# SMPS_Schematic.net
KiCad netlist of a schematic drawn in EAGLE
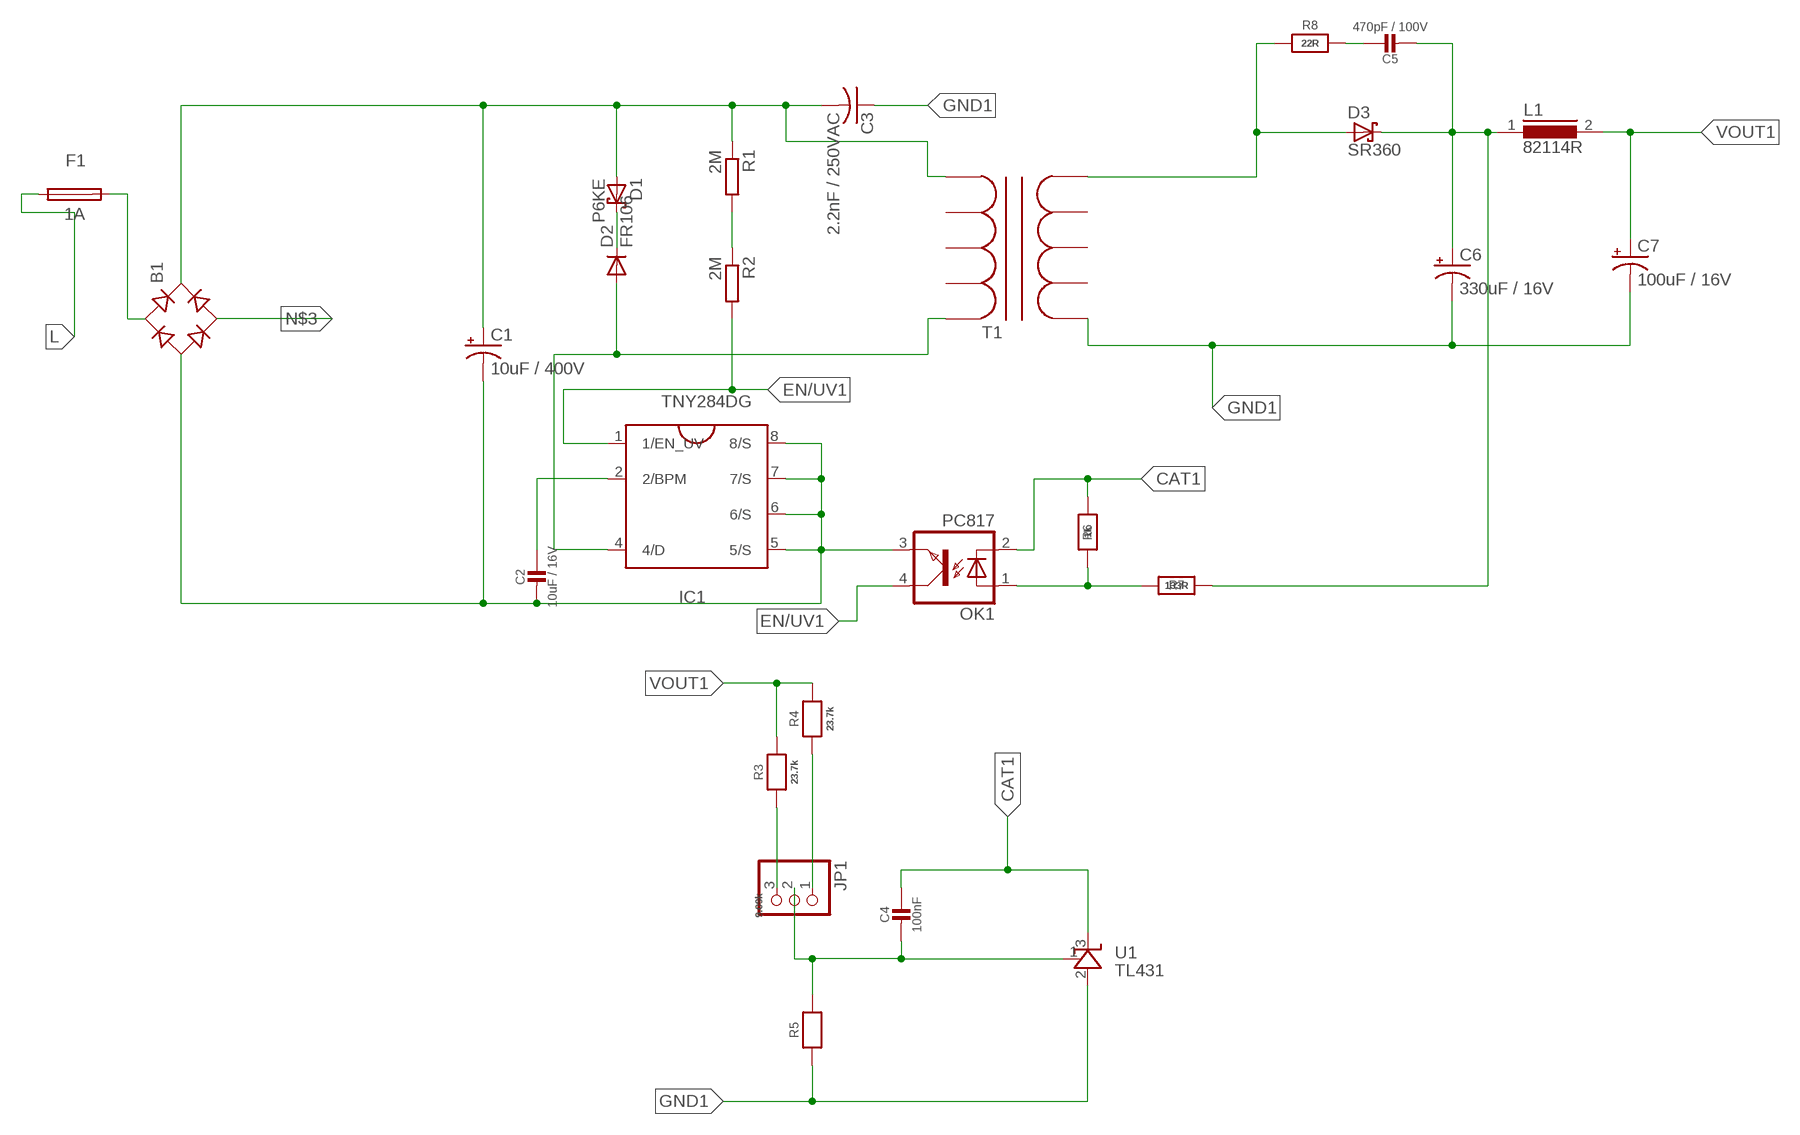
[diagram p0: schematic, sheet 1]

(export (version "E")
  (design (tool "Eeschema 10.0.6"))
  (components
    (comp (ref "B1")
      (value "B-DIL")
      (footprint "eagle-import:B-DIL")
      (libsource (lib "eagle-import") (part "B-DIL"))
    )
    (comp (ref "C1")
      (value "10uF / 400V")
      (footprint "eagle-import:E5-10,5")
      (libsource (lib "eagle-import") (part "CPOL-USE5-10.5"))
    )
    (comp (ref "C2")
      (value "10uF / 16V")
      (footprint "eagle-import:0805-NO")
      (libsource (lib "eagle-import") (part "CAP_CERAMIC0805-NOOUTLINE"))
    )
    (comp (ref "C3")
      (value "2.2nF / 250VAC")
      (footprint "eagle-import:C075-032X103")
      (libsource (lib "eagle-import") (part "C-US075-032X103"))
    )
    (comp (ref "C4")
      (value "100nF")
      (footprint "eagle-import:0805-NO")
      (libsource (lib "eagle-import") (part "CAP_CERAMIC0805-NOOUTLINE"))
    )
    (comp (ref "C5")
      (value "470pF / 100V")
      (footprint "eagle-import:0805-NO")
      (libsource (lib "eagle-import") (part "CAP_CERAMIC0805-NOOUTLINE"))
    )
    (comp (ref "C6")
      (value "330uF / 16V")
      (footprint "eagle-import:E3,5-8")
      (libsource (lib "eagle-import") (part "CPOL-USE3.5-8"))
    )
    (comp (ref "C7")
      (value "100uF / 16V")
      (footprint "eagle-import:E2,5-7")
      (libsource (lib "eagle-import") (part "CPOL-USE2.5-7"))
    )
    (comp (ref "D1")
      (value "P6KE")
      (footprint "eagle-import:CB417-15")
      (libsource (lib "eagle-import") (part "P6KEXX"))
    )
    (comp (ref "D2")
      (value "FR106")
      (footprint "eagle-import:DO41-10")
      (libsource (lib "eagle-import") (part "1N4004"))
    )
    (comp (ref "D3")
      (value "SR360")
      (footprint "eagle-import:C4111-15")
      (libsource (lib "eagle-import") (part "SCHOTTKY-DIODEC4111-15"))
    )
    (comp (ref "F1")
      (value "1A")
      (footprint "eagle-import:TR5")
      (libsource (lib "eagle-import") (part "TR5"))
    )
    (comp (ref "IC1")
      (value "TNY284DG")
      (footprint "eagle-import:SO8-C(D_PACKAGE)")
      (libsource (lib "eagle-import") (part "TNY375-380SO8-C"))
    )
    (comp (ref "JP1")
      (value "PINHD-1X3")
      (footprint "eagle-import:1X03")
      (libsource (lib "eagle-import") (part "PINHD-1X3"))
    )
    (comp (ref "L1")
      (value "82114R")
      (footprint "eagle-import:82114R")
      (libsource (lib "eagle-import") (part "82114R"))
    )
    (comp (ref "OK1")
      (value "PC817")
      (footprint "eagle-import:DIL04")
      (fields (field (name "MPN") "PC817X4J000F"))
      (libsource (lib "eagle-import") (part "PC817"))
    )
    (comp (ref "R1")
      (value "2M")
      (footprint "eagle-import:M1206")
      (libsource (lib "eagle-import") (part "R-EU_M1206"))
    )
    (comp (ref "R2")
      (value "2M")
      (footprint "eagle-import:M1206")
      (libsource (lib "eagle-import") (part "R-EU_M1206"))
    )
    (comp (ref "R3")
      (value "23.7k")
      (footprint "eagle-import:0805-NO")
      (libsource (lib "eagle-import") (part "RESISTOR0805_NOOUTLINE"))
    )
    (comp (ref "R4")
      (value "23.7k")
      (footprint "eagle-import:0805-NO")
      (libsource (lib "eagle-import") (part "RESISTOR0805_NOOUTLINE"))
    )
    (comp (ref "R5")
      (value "9.09k")
      (footprint "eagle-import:0805-NO")
      (libsource (lib "eagle-import") (part "RESISTOR0805_NOOUTLINE"))
    )
    (comp (ref "R6")
      (value "1k")
      (footprint "eagle-import:0805-NO")
      (libsource (lib "eagle-import") (part "RESISTOR0805_NOOUTLINE"))
    )
    (comp (ref "R7")
      (value "133R")
      (footprint "eagle-import:0805-NO")
      (libsource (lib "eagle-import") (part "RESISTOR0805_NOOUTLINE"))
    )
    (comp (ref "R8")
      (value "22R")
      (footprint "eagle-import:0805-NO")
      (libsource (lib "eagle-import") (part "RESISTOR0805_NOOUTLINE"))
    )
    (comp (ref "T1")
      (value "TRANSFORMER_EE16")
      (footprint "eagle-import:EE16")
      (libsource (lib "eagle-import") (part "TRANSFORMER_EE16"))
    )
    (comp (ref "U1")
      (value "TL431")
      (footprint "eagle-import:TO-92")
      (libsource (lib "eagle-import") (part "TL431"))
    )
  )
  (nets
    (net (code "1") (name "CAT1") (class "Default")
      (node (ref "C4") (pin "1") (pinfunction "1_1") (pintype "passive"))
      (node (ref "OK1") (pin "2") (pinfunction "C_2") (pintype "passive"))
      (node (ref "R6") (pin "1") (pinfunction "1_1") (pintype "passive"))
      (node (ref "U1") (pin "3") (pinfunction "C_3") (pintype "bidirectional"))
    )
    (net (code "2") (name "EN{slash}UV1") (class "Default")
      (node (ref "IC1") (pin "1") (pinfunction "1/EN_UV_1") (pintype "bidirectional"))
      (node (ref "OK1") (pin "4") (pinfunction "COL_4") (pintype "passive"))
      (node (ref "R2") (pin "2") (pinfunction "2_2") (pintype "passive"))
    )
    (net (code "3") (name "GND1") (class "Default")
      (node (ref "C3") (pin "1") (pinfunction "1_1") (pintype "passive"))
      (node (ref "C6") (pin "-") (pinfunction "-_-") (pintype "passive"))
      (node (ref "C7") (pin "-") (pinfunction "-_-") (pintype "passive"))
      (node (ref "R5") (pin "1") (pinfunction "1_1") (pintype "passive"))
      (node (ref "T1") (pin "P$6") (pinfunction "P$6_P$6") (pintype "bidirectional"))
      (node (ref "U1") (pin "2") (pinfunction "A_2") (pintype "bidirectional"))
    )
    (net (code "4") (name "L") (class "Default")
      (node (ref "F1") (pin "P$1") (pinfunction "1_P$1") (pintype "passive"))
    )
    (net (code "5") (name "N$3") (class "Default")
      (node (ref "B1") (pin "AC2") (pinfunction "AC2_AC2") (pintype "passive"))
    )
    (net (code "6") (name "Net-(B1-Pad+)") (class "Default")
      (node (ref "B1") (pin "+") (pinfunction "+_+") (pintype "passive"))
      (node (ref "C1") (pin "+") (pinfunction "+_+") (pintype "passive"))
      (node (ref "C3") (pin "2") (pinfunction "2_2") (pintype "passive"))
      (node (ref "D1") (pin "A") (pinfunction "A_A") (pintype "passive"))
      (node (ref "R1") (pin "1") (pinfunction "1_1") (pintype "passive"))
      (node (ref "T1") (pin "P$1") (pinfunction "P$1_P$1") (pintype "bidirectional"))
    )
    (net (code "7") (name "Net-(C5-Pad1)") (class "Default")
      (node (ref "C5") (pin "1") (pinfunction "1_1") (pintype "passive"))
      (node (ref "R8") (pin "2") (pinfunction "2_2") (pintype "passive"))
    )
    (net (code "8") (name "Net-(C5-Pad2)") (class "Default")
      (node (ref "C5") (pin "2") (pinfunction "2_2") (pintype "passive"))
      (node (ref "C6") (pin "+") (pinfunction "+_+") (pintype "passive"))
      (node (ref "D3") (pin "C") (pinfunction "C_C") (pintype "passive"))
      (node (ref "L1") (pin "1") (pinfunction "1_1") (pintype "passive"))
      (node (ref "R7") (pin "2") (pinfunction "2_2") (pintype "passive"))
    )
    (net (code "9") (name "Net-(D1-PadC)") (class "Default")
      (node (ref "D1") (pin "C") (pinfunction "C_C") (pintype "passive"))
      (node (ref "D2") (pin "C") (pinfunction "C_C") (pintype "passive"))
    )
    (net (code "10") (name "Net-(D3-PadA)") (class "Default")
      (node (ref "D3") (pin "A") (pinfunction "A_A") (pintype "passive"))
      (node (ref "R8") (pin "1") (pinfunction "1_1") (pintype "passive"))
      (node (ref "T1") (pin "P$10") (pinfunction "P$10_P$10") (pintype "bidirectional"))
    )
    (net (code "11") (name "Net-(F1-2)") (class "Default")
      (node (ref "B1") (pin "AC1") (pinfunction "AC1_AC1") (pintype "passive"))
      (node (ref "F1") (pin "P$2") (pinfunction "2_P$2") (pintype "passive"))
    )
    (net (code "12") (name "Net-(IC1-2{slash}BPM)") (class "Default")
      (node (ref "C2") (pin "1") (pinfunction "1_1") (pintype "passive"))
      (node (ref "IC1") (pin "2") (pinfunction "2/BPM_2") (pintype "bidirectional"))
    )
    (net (code "13") (name "Net-(IC1-4{slash}D)") (class "Default")
      (node (ref "D2") (pin "A") (pinfunction "A_A") (pintype "passive"))
      (node (ref "IC1") (pin "4") (pinfunction "4/D_4") (pintype "bidirectional"))
      (node (ref "T1") (pin "P$5") (pinfunction "P$5_P$5") (pintype "bidirectional"))
    )
    (net (code "14") (name "Net-(IC1-5{slash}S)") (class "Default")
      (node (ref "B1") (pin "-") (pinfunction "-_-") (pintype "passive"))
      (node (ref "C1") (pin "-") (pinfunction "-_-") (pintype "passive"))
      (node (ref "C2") (pin "2") (pinfunction "2_2") (pintype "passive"))
      (node (ref "IC1") (pin "5") (pinfunction "5/S_5") (pintype "bidirectional"))
      (node (ref "IC1") (pin "6") (pinfunction "6/S_6") (pintype "bidirectional"))
      (node (ref "IC1") (pin "7") (pinfunction "7/S_7") (pintype "bidirectional"))
      (node (ref "IC1") (pin "8") (pinfunction "8/S_8") (pintype "bidirectional"))
      (node (ref "OK1") (pin "3") (pinfunction "EMIT_3") (pintype "passive"))
    )
    (net (code "15") (name "Net-(JP1-Pad1)") (class "Default")
      (node (ref "JP1") (pin "1") (pinfunction "1_1") (pintype "passive"))
      (node (ref "R4") (pin "1") (pinfunction "1_1") (pintype "passive"))
    )
    (net (code "16") (name "Net-(JP1-Pad3)") (class "Default")
      (node (ref "JP1") (pin "3") (pinfunction "3_3") (pintype "passive"))
      (node (ref "R3") (pin "1") (pinfunction "1_1") (pintype "passive"))
    )
    (net (code "17") (name "Net-(OK1-A)") (class "Default")
      (node (ref "OK1") (pin "1") (pinfunction "A_1") (pintype "passive"))
      (node (ref "R6") (pin "2") (pinfunction "2_2") (pintype "passive"))
      (node (ref "R7") (pin "1") (pinfunction "1_1") (pintype "passive"))
    )
    (net (code "18") (name "Net-(R1-Pad2)") (class "Default")
      (node (ref "R1") (pin "2") (pinfunction "2_2") (pintype "passive"))
      (node (ref "R2") (pin "1") (pinfunction "1_1") (pintype "passive"))
    )
    (net (code "19") (name "Net-(U1-REF)") (class "Default")
      (node (ref "C4") (pin "2") (pinfunction "2_2") (pintype "passive"))
      (node (ref "JP1") (pin "2") (pinfunction "2_2") (pintype "passive"))
      (node (ref "R5") (pin "2") (pinfunction "2_2") (pintype "passive"))
      (node (ref "U1") (pin "1") (pinfunction "REF_1") (pintype "input"))
    )
    (net (code "20") (name "VOUT1") (class "Default")
      (node (ref "C7") (pin "+") (pinfunction "+_+") (pintype "passive"))
      (node (ref "L1") (pin "2") (pinfunction "2_2") (pintype "passive"))
      (node (ref "R3") (pin "2") (pinfunction "2_2") (pintype "passive"))
      (node (ref "R4") (pin "2") (pinfunction "2_2") (pintype "passive"))
    )
    (net (code "21") (name "unconnected-(T1-PadP$2)") (class "Default")
      (node (ref "T1") (pin "P$2") (pinfunction "P$2_P$2") (pintype "bidirectional"))
    )
    (net (code "22") (name "unconnected-(T1-PadP$3)") (class "Default")
      (node (ref "T1") (pin "P$3") (pinfunction "P$3_P$3") (pintype "bidirectional"))
    )
    (net (code "23") (name "unconnected-(T1-PadP$4)") (class "Default")
      (node (ref "T1") (pin "P$4") (pinfunction "P$4_P$4") (pintype "bidirectional"))
    )
    (net (code "24") (name "unconnected-(T1-PadP$7)") (class "Default")
      (node (ref "T1") (pin "P$7") (pinfunction "P$7_P$7") (pintype "bidirectional"))
    )
    (net (code "25") (name "unconnected-(T1-PadP$8)") (class "Default")
      (node (ref "T1") (pin "P$8") (pinfunction "P$8_P$8") (pintype "bidirectional"))
    )
    (net (code "26") (name "unconnected-(T1-PadP$9)") (class "Default")
      (node (ref "T1") (pin "P$9") (pinfunction "P$9_P$9") (pintype "bidirectional"))
    )
  )
)
